# Ethernet_Connector.net
KiCad netlist of a schematic drawn in Altium Designer
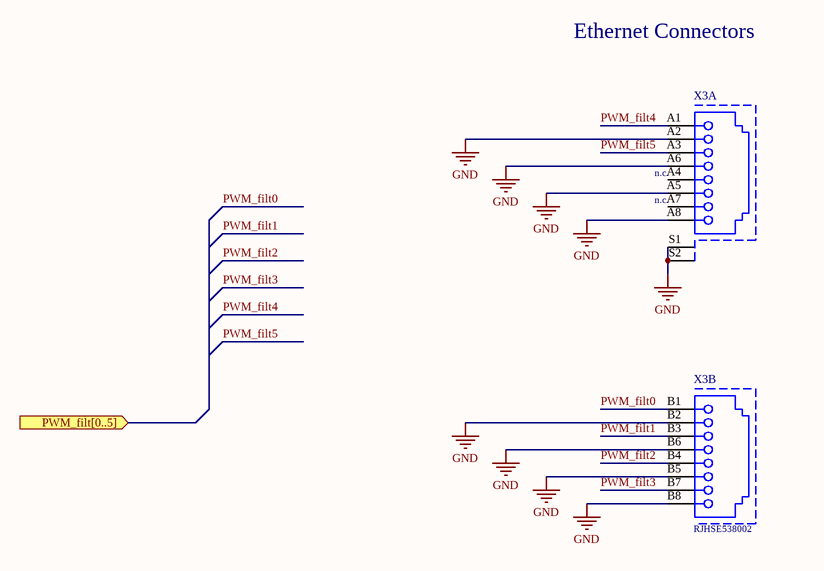
[diagram p0: Ethernet_Connector.SchDoc]

(export (version "E")
  (design (tool "Eeschema 10.0.6"))
  (components
    (comp (ref "X3")
      (value "RJHSE538002")
      (footprint "RJHSE-5380-02")
      (description "CAT5, RJ45 Connector, 1x2")
      (fields
        (field (name "MANUFACTURER PART NUMBER") "RJHSE538002")
        (field (name "MANUFACTURER") "Amphenol")
        (field (name "CREATED FROM") "MGremer")
      )
      (libsource (lib "user") (part "RJHSE-5380-02"))
    )
  )
  (nets
    (net (code "1") (name "/PWM_filt0") (class "Default")
      (node (ref "X3") (pin "B1") (pinfunction "B1_B1") (pintype "passive"))
    )
    (net (code "2") (name "/PWM_filt1") (class "Default")
      (node (ref "X3") (pin "B3") (pinfunction "B3_B3") (pintype "passive"))
    )
    (net (code "3") (name "/PWM_filt2") (class "Default")
      (node (ref "X3") (pin "B4") (pinfunction "B4_B4") (pintype "passive"))
    )
    (net (code "4") (name "/PWM_filt3") (class "Default")
      (node (ref "X3") (pin "B7") (pinfunction "B7_B7") (pintype "passive"))
    )
    (net (code "5") (name "/PWM_filt4") (class "Default")
      (node (ref "X3") (pin "A1") (pinfunction "A1_A1") (pintype "passive"))
    )
    (net (code "6") (name "/PWM_filt5") (class "Default")
      (node (ref "X3") (pin "A3") (pinfunction "A3_A3") (pintype "passive"))
    )
    (net (code "8") (name "GND") (class "Default")
      (node (ref "X3") (pin "A2") (pinfunction "A2_A2") (pintype "passive"))
      (node (ref "X3") (pin "A5") (pinfunction "A5_A5") (pintype "passive"))
      (node (ref "X3") (pin "A6") (pinfunction "A6_A6") (pintype "passive"))
      (node (ref "X3") (pin "A8") (pinfunction "A8_A8") (pintype "passive"))
      (node (ref "X3") (pin "B2") (pinfunction "B2_B2") (pintype "passive"))
      (node (ref "X3") (pin "B5") (pinfunction "B5_B5") (pintype "passive"))
      (node (ref "X3") (pin "B6") (pinfunction "B6_B6") (pintype "passive"))
      (node (ref "X3") (pin "B8") (pinfunction "B8_B8") (pintype "passive"))
      (node (ref "X3") (pin "S1") (pinfunction "S1_S1") (pintype "passive"))
      (node (ref "X3") (pin "S2") (pinfunction "S2_S2") (pintype "passive"))
    )
    (net (code "9") (name "unconnected-(X3-PadA4)") (class "Default")
      (node (ref "X3") (pin "A4") (pinfunction "A4_A4") (pintype "passive"))
    )
    (net (code "10") (name "unconnected-(X3-PadA7)") (class "Default")
      (node (ref "X3") (pin "A7") (pinfunction "A7_A7") (pintype "passive"))
    )
  )
)
